# MCU.net
KiCad netlist of a schematic drawn in Altium Designer
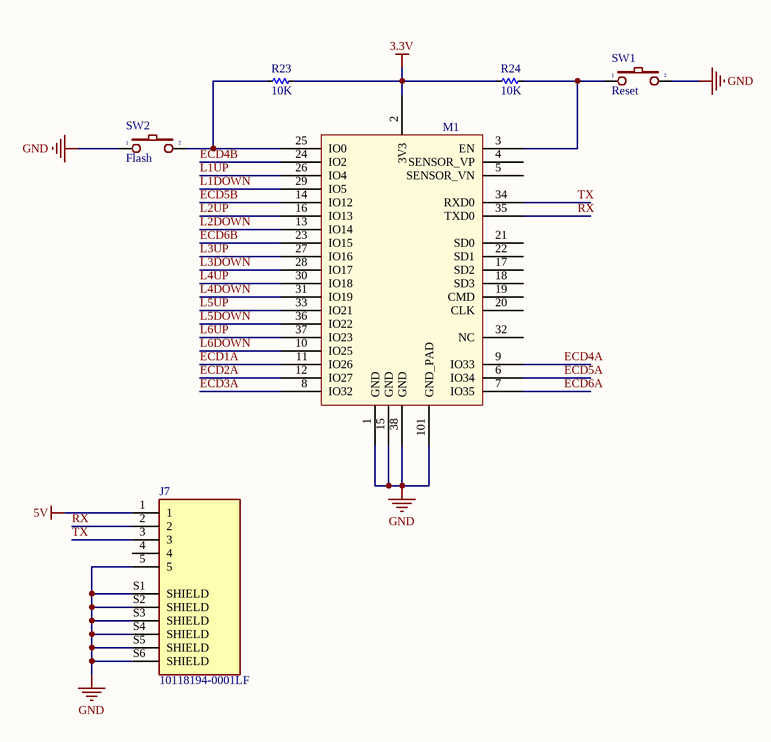
[diagram p0: MCU.SchDoc]

(export (version "E")
  (design (tool "Eeschema 10.0.6"))
  (components
    (comp (ref "J7")
      (value "10118194-0001LF")
      (footprint "AMPHENOL_10118194-0001LF")
      (description "USB - micro B USB 2.0 Receptacle Connector 5 Position Surface Mount, Right Angle; Through Hole")
      (fields (field (name "MF") "Amphenol ICC"))
      (libsource (lib "10118194-0001LF") (part "10118194-0001LF"))
    )
    (comp (ref "M1")
      (value "ESP32S_Module")
      (footprint "ESP32S")
      (description "Esp-32S")
      (libsource (lib "ESP32S") (part "ESP32S_Module"))
    )
    (comp (ref "R23")
      (value "10K")
      (footprint "RES-SMD-0805")
      (description "Resistor")
      (fields
        (field (name "MANUFACTURER") "Generic Components")
        (field (name "PUBLISHER") "Altium Hobart Technology Centre")
      )
      (libsource (lib "LIBRARY") (part "Res-SMD"))
    )
    (comp (ref "R24")
      (value "10K")
      (footprint "RES-SMD-0805")
      (description "Resistor")
      (fields
        (field (name "MANUFACTURER") "Generic Components")
        (field (name "PUBLISHER") "Altium Hobart Technology Centre")
      )
      (libsource (lib "LIBRARY") (part "Res-SMD"))
    )
    (comp (ref "SW1")
      (value "Reset")
      (footprint "SW1-SMD")
      (description "Switch button 2 pin")
      (libsource (lib "LIBRARY") (part "SW2"))
    )
    (comp (ref "SW2")
      (value "Flash")
      (footprint "SW-DIP1-1")
      (description "Switch button 2 pin")
      (libsource (lib "LIBRARY") (part "SW2"))
    )
  )
  (nets
    (net (code "1") (name "/ECD1A") (class "Default")
      (node (ref "M1") (pin "11") (pinfunction "IO26_11") (pintype "passive"))
    )
    (net (code "2") (name "/ECD2A") (class "Default")
      (node (ref "M1") (pin "12") (pinfunction "IO27_12") (pintype "passive"))
    )
    (net (code "3") (name "/ECD3A") (class "Default")
      (node (ref "M1") (pin "8") (pinfunction "IO32_8") (pintype "passive"))
    )
    (net (code "4") (name "/ECD4A") (class "Default")
      (node (ref "M1") (pin "9") (pinfunction "IO33_9") (pintype "passive"))
    )
    (net (code "5") (name "/ECD4B") (class "Default")
      (node (ref "M1") (pin "24") (pinfunction "IO2_24") (pintype "passive"))
    )
    (net (code "6") (name "/ECD5A") (class "Default")
      (node (ref "M1") (pin "6") (pinfunction "IO34_6") (pintype "passive"))
    )
    (net (code "7") (name "/ECD5B") (class "Default")
      (node (ref "M1") (pin "14") (pinfunction "IO12_14") (pintype "passive"))
    )
    (net (code "8") (name "/ECD6A") (class "Default")
      (node (ref "M1") (pin "7") (pinfunction "IO35_7") (pintype "passive"))
    )
    (net (code "9") (name "/ECD6B") (class "Default")
      (node (ref "M1") (pin "23") (pinfunction "IO15_23") (pintype "passive"))
    )
    (net (code "10") (name "/L1DOWN") (class "Default")
      (node (ref "M1") (pin "29") (pinfunction "IO5_29") (pintype "passive"))
    )
    (net (code "11") (name "/L1UP") (class "Default")
      (node (ref "M1") (pin "26") (pinfunction "IO4_26") (pintype "passive"))
    )
    (net (code "12") (name "/L2DOWN") (class "Default")
      (node (ref "M1") (pin "13") (pinfunction "IO14_13") (pintype "passive"))
    )
    (net (code "13") (name "/L2UP") (class "Default")
      (node (ref "M1") (pin "16") (pinfunction "IO13_16") (pintype "passive"))
    )
    (net (code "14") (name "/L3DOWN") (class "Default")
      (node (ref "M1") (pin "28") (pinfunction "IO17_28") (pintype "passive"))
    )
    (net (code "15") (name "/L3UP") (class "Default")
      (node (ref "M1") (pin "27") (pinfunction "IO16_27") (pintype "passive"))
    )
    (net (code "16") (name "/L4DOWN") (class "Default")
      (node (ref "M1") (pin "31") (pinfunction "IO19_31") (pintype "passive"))
    )
    (net (code "17") (name "/L4UP") (class "Default")
      (node (ref "M1") (pin "30") (pinfunction "IO18_30") (pintype "passive"))
    )
    (net (code "18") (name "/L5DOWN") (class "Default")
      (node (ref "M1") (pin "36") (pinfunction "IO22_36") (pintype "passive"))
    )
    (net (code "19") (name "/L5UP") (class "Default")
      (node (ref "M1") (pin "33") (pinfunction "IO21_33") (pintype "passive"))
    )
    (net (code "20") (name "/L6DOWN") (class "Default")
      (node (ref "M1") (pin "10") (pinfunction "IO25_10") (pintype "passive"))
    )
    (net (code "21") (name "/L6UP") (class "Default")
      (node (ref "M1") (pin "37") (pinfunction "IO23_37") (pintype "passive"))
    )
    (net (code "22") (name "/RX") (class "Default")
      (node (ref "J7") (pin "2") (pinfunction "2_2") (pintype "passive"))
      (node (ref "M1") (pin "35") (pinfunction "TXD0_35") (pintype "passive"))
    )
    (net (code "23") (name "/TX") (class "Default")
      (node (ref "J7") (pin "3") (pinfunction "3_3") (pintype "passive"))
      (node (ref "M1") (pin "34") (pinfunction "RXD0_34") (pintype "passive"))
    )
    (net (code "24") (name "3.3V") (class "Default")
      (node (ref "M1") (pin "2") (pinfunction "3V3_2") (pintype "power_in"))
      (node (ref "R23") (pin "1") (pinfunction "1_1") (pintype "passive"))
      (node (ref "R24") (pin "2") (pinfunction "2_2") (pintype "passive"))
    )
    (net (code "25") (name "5V") (class "Default")
      (node (ref "J7") (pin "1") (pinfunction "1_1") (pintype "passive"))
    )
    (net (code "26") (name "GND") (class "Default")
      (node (ref "J7") (pin "5") (pinfunction "5_5") (pintype "passive"))
      (node (ref "J7") (pin "S1") (pinfunction "SHIELD_S1") (pintype "passive"))
      (node (ref "J7") (pin "S2") (pinfunction "SHIELD_S2") (pintype "passive"))
      (node (ref "J7") (pin "S3") (pinfunction "SHIELD_S3") (pintype "passive"))
      (node (ref "J7") (pin "S4") (pinfunction "SHIELD_S4") (pintype "passive"))
      (node (ref "J7") (pin "S5") (pinfunction "SHIELD_S5") (pintype "passive"))
      (node (ref "J7") (pin "S6") (pinfunction "SHIELD_S6") (pintype "passive"))
      (node (ref "M1") (pin "1") (pinfunction "GND_1") (pintype "power_in"))
      (node (ref "M1") (pin "101") (pinfunction "GND_PAD_101") (pintype "power_in"))
      (node (ref "M1") (pin "15") (pinfunction "GND_15") (pintype "power_in"))
      (node (ref "M1") (pin "38") (pinfunction "GND_38") (pintype "power_in"))
      (node (ref "SW1") (pin "2") (pinfunction "2_2") (pintype "passive"))
      (node (ref "SW2") (pin "1") (pinfunction "1_1") (pintype "passive"))
    )
    (net (code "27") (name "Net-(M1-EN)") (class "Default")
      (node (ref "M1") (pin "3") (pinfunction "EN_3") (pintype "power_in"))
      (node (ref "R24") (pin "1") (pinfunction "1_1") (pintype "passive"))
      (node (ref "SW1") (pin "1") (pinfunction "1_1") (pintype "passive"))
    )
    (net (code "28") (name "Net-(M1-IO0)") (class "Default")
      (node (ref "M1") (pin "25") (pinfunction "IO0_25") (pintype "passive"))
      (node (ref "R23") (pin "2") (pinfunction "2_2") (pintype "passive"))
      (node (ref "SW2") (pin "2") (pinfunction "2_2") (pintype "passive"))
    )
    (net (code "29") (name "unconnected-(J7-Pad4)") (class "Default")
      (node (ref "J7") (pin "4") (pinfunction "4_4") (pintype "passive"))
    )
    (net (code "30") (name "unconnected-(M1-CLK-Pad20)") (class "Default")
      (node (ref "M1") (pin "20") (pinfunction "CLK_20") (pintype "passive"))
    )
    (net (code "31") (name "unconnected-(M1-CMD-Pad19)") (class "Default")
      (node (ref "M1") (pin "19") (pinfunction "CMD_19") (pintype "passive"))
    )
    (net (code "32") (name "unconnected-(M1-NC-Pad32)") (class "Default")
      (node (ref "M1") (pin "32") (pinfunction "NC_32") (pintype "passive"))
    )
    (net (code "33") (name "unconnected-(M1-SD0-Pad21)") (class "Default")
      (node (ref "M1") (pin "21") (pinfunction "SD0_21") (pintype "passive"))
    )
    (net (code "34") (name "unconnected-(M1-SD1-Pad22)") (class "Default")
      (node (ref "M1") (pin "22") (pinfunction "SD1_22") (pintype "passive"))
    )
    (net (code "35") (name "unconnected-(M1-SD2-Pad17)") (class "Default")
      (node (ref "M1") (pin "17") (pinfunction "SD2_17") (pintype "passive"))
    )
    (net (code "36") (name "unconnected-(M1-SD3-Pad18)") (class "Default")
      (node (ref "M1") (pin "18") (pinfunction "SD3_18") (pintype "passive"))
    )
    (net (code "37") (name "unconnected-(M1-SENSOR_VN-Pad5)") (class "Default")
      (node (ref "M1") (pin "5") (pinfunction "SENSOR_VN_5") (pintype "passive"))
    )
    (net (code "38") (name "unconnected-(M1-SENSOR_VP-Pad4)") (class "Default")
      (node (ref "M1") (pin "4") (pinfunction "SENSOR_VP_4") (pintype "passive"))
    )
  )
)
